# LEDcircuits_PhaseV.net
KiCad netlist of a schematic drawn in Altium Designer
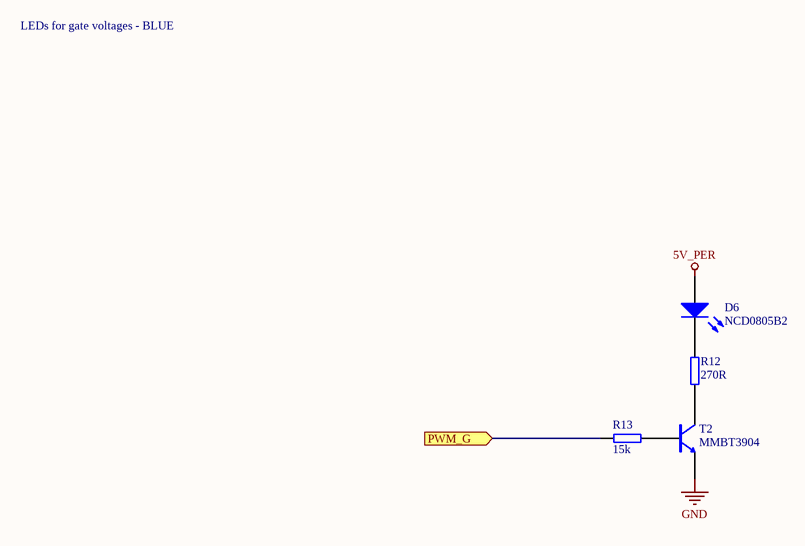
[diagram p0: LEDcircuits_PhaseV.SchDoc]

(export (version "E")
  (design (tool "Eeschema 10.0.6"))
  (components
    (comp (ref "D6")
      (value "NCD0805B2")
      (footprint "LEDM2012X80N")
      (description "Blue 0805 Light Emitting Diodes (LED) ROHS")
      (fields
        (field (name "MANUFACTURER") "Foshan NationStar Optoelectronics")
        (field (name "LCSC PART NUMBER") "C84259")
        (field (name "CREATED FROM") "NDiringer")
      )
      (libsource (lib "user") (part "LED_Blue"))
    )
    (comp (ref "R12")
      (value "270R")
      (footprint "RES 0603_1608")
      (fields
        (field (name "MANUFACTURER PART NUMBER") "0603WAF2700T5E")
        (field (name "MANUFACTURER") "UNI-ROYAL(Uniroyal Elec)")
        (field (name "TOLERANCE") "1%")
        (field (name "CREATED FROM") "NDiringer")
      )
      (libsource (lib "user") (part "Resistor"))
    )
    (comp (ref "R13")
      (value "15k")
      (footprint "RES 0603_1608")
      (description "SMD resistor E24 series")
      (fields
        (field (name "MANUFACTURER PART NUMBER") "RK73B1JTTD153J")
        (field (name "MANUFACTURER") "KOA Speer")
        (field (name "CREATED FROM") "MGremer")
      )
      (libsource (lib "user") (part "Resistor"))
    )
    (comp (ref "T2")
      (value "MMBT3904")
      (footprint "SOT95P280X145-3N")
      (fields
        (field (name "MANUFACTURER") "Jiangsu Changjing Electronics Technology Co., Ltd.")
        (field (name "LCSC PART NUMBER") "C20526")
        (field (name "CREATED FROM") "NDiringer")
      )
      (libsource (lib "user") (part "NPN-SOT23"))
    )
  )
  (nets
    (net (code "1") (name "/PWM_G") (class "Default")
      (node (ref "R13") (pin "1") (pinfunction "1_1") (pintype "passive"))
    )
    (net (code "2") (name "5V_PER") (class "Default")
      (node (ref "D6") (pin "2") (pinfunction "A_2") (pintype "passive"))
    )
    (net (code "3") (name "GND") (class "Default")
      (node (ref "T2") (pin "2") (pinfunction "EMITTER_2") (pintype "passive"))
    )
    (net (code "4") (name "Net-(D6-K)") (class "Default")
      (node (ref "D6") (pin "1") (pinfunction "K_1") (pintype "passive"))
      (node (ref "R12") (pin "2") (pinfunction "2_2") (pintype "passive"))
    )
    (net (code "5") (name "Net-(T2-BASIS)") (class "Default")
      (node (ref "R13") (pin "2") (pinfunction "2_2") (pintype "passive"))
      (node (ref "T2") (pin "1") (pinfunction "BASIS_1") (pintype "passive"))
    )
    (net (code "6") (name "Net-(T2-COLLECTOR)") (class "Default")
      (node (ref "R12") (pin "1") (pinfunction "1_1") (pintype "passive"))
      (node (ref "T2") (pin "3") (pinfunction "COLLECTOR_3") (pintype "passive"))
    )
  )
)
